# EDU_High-Speed-Design_Power_3V0.net
KiCad netlist of a schematic drawn in Altium Designer
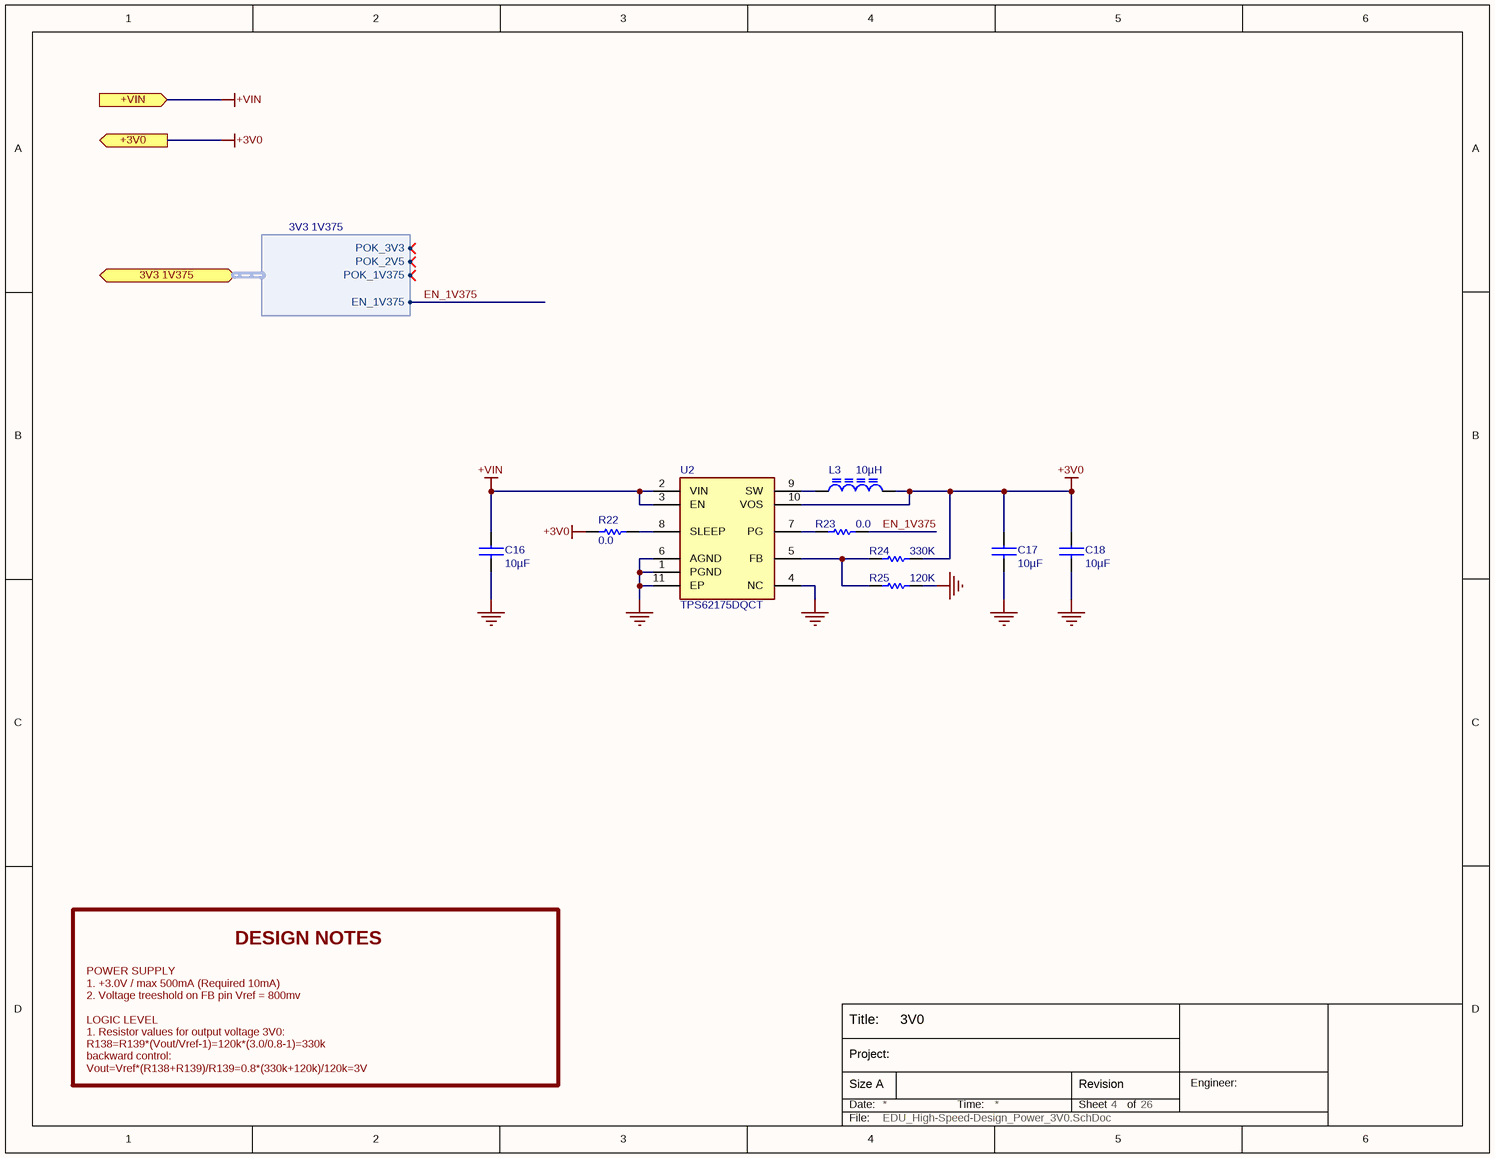
[diagram p0: EDU_High-Speed-Design_Power_3V0.SchDoc]

(export (version "E")
  (design (tool "Eeschema 10.0.6"))
  (components
    (comp (ref "C16")
      (value "10µF")
      (footprint "C1206")
      (description "CAP CER 10UF 35V X5R 1206")
      (fields (field (name "VOLTAGE") "35V"))
      (libsource (lib "EDU_High-Speed-Design") (part "GRM31CR6YA106KA12L"))
    )
    (comp (ref "C17")
      (value "10µF")
      (footprint "C0603")
      (description "CAP CER 10UF 6.3V X5R 20% 0603")
      (fields (field (name "VOLTAGE") "6.3V"))
      (libsource (lib "EDU_High-Speed-Design") (part "C1608X5R0J106M"))
    )
    (comp (ref "C18")
      (value "10µF")
      (footprint "C0603")
      (description "CAP CER 10UF 6.3V X5R 20% 0603")
      (fields (field (name "VOLTAGE") "6.3V"))
      (libsource (lib "EDU_High-Speed-Design") (part "C1608X5R0J106M"))
    )
    (comp (ref "L3")
      (value "10µH")
      (footprint "VLCF4020")
      (description "INDUCTOR POWER 10UH .85A SMD")
      (libsource (lib "EDU_High-Speed-Design") (part "VLCF4020T-100MR85"))
    )
    (comp (ref "R22")
      (value "0.0")
      (footprint "R0402")
      (description "RES 0.0 OHM 1/16W 0402 SMD")
      (libsource (lib "EDU_High-Speed-Design") (part "RC0402JR-070RL"))
    )
    (comp (ref "R23")
      (value "0.0")
      (footprint "R0402")
      (description "RES 0.0 OHM 1/16W 0402 SMD")
      (libsource (lib "EDU_High-Speed-Design") (part "RC0402JR-070RL"))
    )
    (comp (ref "R24")
      (value "330K")
      (footprint "R0402")
      (description "RES 330K OHM 1/16W 1% 0402 SMD")
      (libsource (lib "EDU_High-Speed-Design") (part "CRCW0402330KFKED"))
    )
    (comp (ref "R25")
      (value "120K")
      (footprint "R0402")
      (description "RES 120K OHM 1/16W 1% 0402 SMD")
      (libsource (lib "EDU_High-Speed-Design") (part "RC0402FR-07120KL"))
    )
    (comp (ref "U2")
      (value "TPS62175DQCT")
      (footprint "TPS62175DQCT")
      (description "IC REG BUCK SYNC ADJ 0.5A 10WSON")
      (libsource (lib "EDU_High-Speed-Design") (part "TPS62175DQCT"))
    )
  )
  (nets
    (net (code "3") (name "+3V0") (class "Default")
      (node (ref "C17") (pin "1") (pinfunction "1_1") (pintype "passive"))
      (node (ref "C18") (pin "1") (pinfunction "1_1") (pintype "passive"))
      (node (ref "L3") (pin "2") (pinfunction "2_2") (pintype "passive"))
      (node (ref "R22") (pin "1") (pinfunction "1_1") (pintype "passive"))
      (node (ref "R24") (pin "1") (pinfunction "1_1") (pintype "passive"))
      (node (ref "U2") (pin "10") (pinfunction "VOS_10") (pintype "passive"))
    )
    (net (code "4") (name "+VIN") (class "Default")
      (node (ref "C16") (pin "1") (pinfunction "1_1") (pintype "passive"))
      (node (ref "U2") (pin "2") (pinfunction "VIN_2") (pintype "passive"))
      (node (ref "U2") (pin "3") (pinfunction "EN_3") (pintype "passive"))
    )
    (net (code "5") (name "/EN_1V375") (class "Default")
      (node (ref "R23") (pin "2") (pinfunction "2_2") (pintype "passive"))
    )
    (net (code "7") (name "GND") (class "Default")
      (node (ref "C16") (pin "2") (pinfunction "2_2") (pintype "passive"))
      (node (ref "C17") (pin "2") (pinfunction "2_2") (pintype "passive"))
      (node (ref "C18") (pin "2") (pinfunction "2_2") (pintype "passive"))
      (node (ref "R25") (pin "1") (pinfunction "1_1") (pintype "passive"))
      (node (ref "U2") (pin "1") (pinfunction "PGND_1") (pintype "passive"))
      (node (ref "U2") (pin "11") (pinfunction "EP_11") (pintype "passive"))
      (node (ref "U2") (pin "4") (pinfunction "NC_4") (pintype "passive"))
      (node (ref "U2") (pin "6") (pinfunction "AGND_6") (pintype "passive"))
    )
    (net (code "8") (name "Net-(U2-FB)") (class "Default")
      (node (ref "R24") (pin "2") (pinfunction "2_2") (pintype "passive"))
      (node (ref "R25") (pin "2") (pinfunction "2_2") (pintype "passive"))
      (node (ref "U2") (pin "5") (pinfunction "FB_5") (pintype "passive"))
    )
    (net (code "9") (name "Net-(U2-PG)") (class "Default")
      (node (ref "R23") (pin "1") (pinfunction "1_1") (pintype "passive"))
      (node (ref "U2") (pin "7") (pinfunction "PG_7") (pintype "passive"))
    )
    (net (code "10") (name "Net-(U2-SLEEP)") (class "Default")
      (node (ref "R22") (pin "2") (pinfunction "2_2") (pintype "passive"))
      (node (ref "U2") (pin "8") (pinfunction "SLEEP_8") (pintype "passive"))
    )
    (net (code "11") (name "Net-(U2-SW)") (class "Default")
      (node (ref "L3") (pin "1") (pinfunction "1_1") (pintype "passive"))
      (node (ref "U2") (pin "9") (pinfunction "SW_9") (pintype "passive"))
    )
  )
)
